# Mode1.net
KiCad netlist of a schematic drawn in Altium Designer
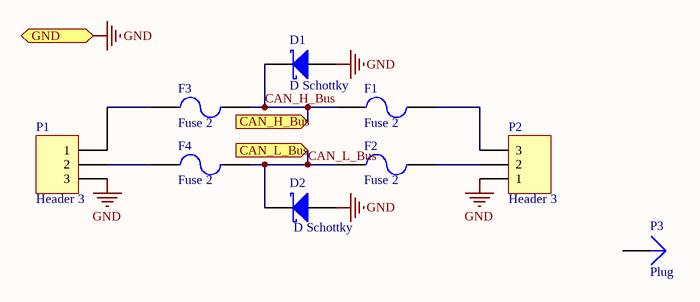
[diagram p0: Mode1.SchDoc]

(export (version "E")
  (design (tool "Eeschema 10.0.6"))
  (components
    (comp (ref "D1")
      (value "D Schottky")
      (footprint "SMB")
      (description "Schottky Diode")
      (fields (field (name "PUBLISHER") "Altium Limited"))
      (libsource (lib "Miscellaneous Devices") (part "D Schottky"))
    )
    (comp (ref "D2")
      (value "D Schottky")
      (footprint "SMB")
      (description "Schottky Diode")
      (fields (field (name "PUBLISHER") "Altium Limited"))
      (libsource (lib "Miscellaneous Devices") (part "D Schottky"))
    )
    (comp (ref "F1")
      (value "Fuse 2")
      (footprint "12Z-2010")
      (description "Fuse")
      (fields (field (name "PUBLISHER") "Altium Limited"))
      (libsource (lib "Miscellaneous Devices") (part "Fuse 2"))
    )
    (comp (ref "F2")
      (value "Fuse 2")
      (footprint "12Z-2010")
      (description "Fuse")
      (fields (field (name "PUBLISHER") "Altium Limited"))
      (libsource (lib "Miscellaneous Devices") (part "Fuse 2"))
    )
    (comp (ref "F3")
      (value "Fuse 2")
      (footprint "12Z-2010")
      (description "Fuse")
      (fields (field (name "PUBLISHER") "Altium Limited"))
      (libsource (lib "Miscellaneous Devices") (part "Fuse 2"))
    )
    (comp (ref "F4")
      (value "Fuse 2")
      (footprint "12Z-2010")
      (description "Fuse")
      (fields (field (name "PUBLISHER") "Altium Limited"))
      (libsource (lib "Miscellaneous Devices") (part "Fuse 2"))
    )
    (comp (ref "P1")
      (value "Header 3")
      (footprint "DZ-3-5.08")
      (description "Header, 3-Pin")
      (fields (field (name "PUBLISHER") "Altium Limited"))
      (libsource (lib "Miscellaneous Connectors") (part "Header 3"))
    )
    (comp (ref "P2")
      (value "Header 3")
      (footprint "DZ-3-5.08")
      (description "Header, 3-Pin")
      (fields (field (name "PUBLISHER") "Altium Limited"))
      (libsource (lib "") (part "Header 3_1"))
    )
    (comp (ref "P3")
      (value "Plug")
      (footprint "定位孔 Φ3.2")
      (fields (field (name "PUBLISHER") "Altium Limited"))
      (libsource (lib "Miscellaneous Connectors") (part "Plug"))
    )
  )
  (nets
    (net (code "1") (name "/CAN_H_Bus") (class "Default")
      (node (ref "D1") (pin "2") (pinfunction "K_2") (pintype "passive"))
      (node (ref "F1") (pin "1") (pinfunction "1_1") (pintype "passive"))
      (node (ref "F3") (pin "1") (pinfunction "1_1") (pintype "passive"))
    )
    (net (code "2") (name "/CAN_L_Bus") (class "Default")
      (node (ref "D2") (pin "2") (pinfunction "K_2") (pintype "passive"))
      (node (ref "F2") (pin "1") (pinfunction "1_1") (pintype "passive"))
      (node (ref "F4") (pin "1") (pinfunction "1_1") (pintype "passive"))
    )
    (net (code "3") (name "GND") (class "Default")
      (node (ref "D1") (pin "1") (pinfunction "A_1") (pintype "passive"))
      (node (ref "D2") (pin "1") (pinfunction "A_1") (pintype "passive"))
      (node (ref "P1") (pin "3") (pinfunction "3_3") (pintype "passive"))
      (node (ref "P2") (pin "1") (pinfunction "1_1") (pintype "passive"))
    )
    (net (code "4") (name "Net-(F1-Pad2)") (class "Default")
      (node (ref "F1") (pin "2") (pinfunction "2_2") (pintype "passive"))
      (node (ref "P2") (pin "3") (pinfunction "3_3") (pintype "passive"))
    )
    (net (code "5") (name "Net-(F2-Pad2)") (class "Default")
      (node (ref "F2") (pin "2") (pinfunction "2_2") (pintype "passive"))
      (node (ref "P2") (pin "2") (pinfunction "2_2") (pintype "passive"))
    )
    (net (code "6") (name "Net-(F3-Pad2)") (class "Default")
      (node (ref "F3") (pin "2") (pinfunction "2_2") (pintype "passive"))
      (node (ref "P1") (pin "1") (pinfunction "1_1") (pintype "passive"))
    )
    (net (code "7") (name "Net-(F4-Pad2)") (class "Default")
      (node (ref "F4") (pin "2") (pinfunction "2_2") (pintype "passive"))
      (node (ref "P1") (pin "2") (pinfunction "2_2") (pintype "passive"))
    )
    (net (code "8") (name "unconnected-(P3-Pad1)") (class "Default")
      (node (ref "P3") (pin "1") (pinfunction "1_1") (pintype "passive"))
    )
  )
)
